# VolCon.net
KiCad netlist of a schematic drawn in EAGLE
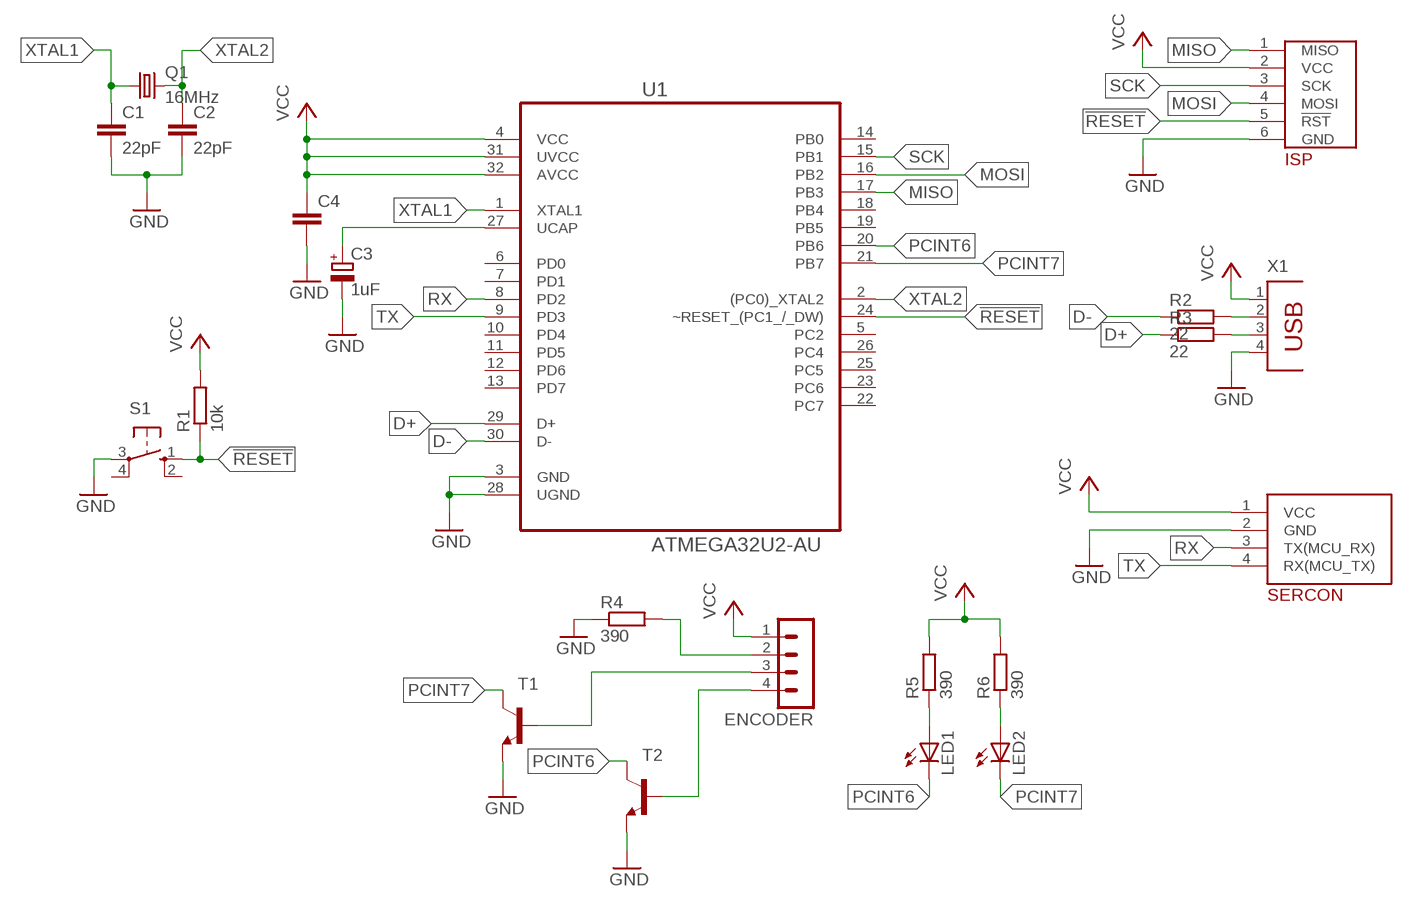
[diagram p0: schematic, sheet 1]

(export (version "E")
  (design (tool "Eeschema 10.0.6"))
  (components
    (comp (ref "C1")
      (value "22pF")
      (footprint "eagle-import:C050-024X044")
      (libsource (lib "eagle-import") (part "C-EU050-024X044"))
    )
    (comp (ref "C2")
      (value "22pF")
      (footprint "eagle-import:C050-024X044")
      (libsource (lib "eagle-import") (part "C-EU050-024X044"))
    )
    (comp (ref "C3")
      (value "1uF")
      (footprint "eagle-import:E5-6")
      (libsource (lib "eagle-import") (part "CPOL-EUE5-6"))
    )
    (comp (ref "C4")
      (value "C-EU050-025X075")
      (footprint "eagle-import:C050-025X075")
      (libsource (lib "eagle-import") (part "C-EU050-025X075"))
    )
    (comp (ref "ENCODER")
      (value "MA04-1")
      (footprint "eagle-import:MA04-1")
      (libsource (lib "eagle-import") (part "MA04-1"))
    )
    (comp (ref "LED1")
      (value "LED5MM")
      (footprint "eagle-import:LED5MM")
      (libsource (lib "eagle-import") (part "LED5MM"))
    )
    (comp (ref "LED2")
      (value "LED5MM")
      (footprint "eagle-import:LED5MM")
      (libsource (lib "eagle-import") (part "LED5MM"))
    )
    (comp (ref "Q1")
      (value "16MHz")
      (footprint "eagle-import:HC49_S")
      (libsource (lib "eagle-import") (part "CRYSTALHC49S"))
    )
    (comp (ref "R1")
      (value "10k")
      (footprint "eagle-import:0204_7")
      (libsource (lib "eagle-import") (part "R-EU_0204/7"))
    )
    (comp (ref "R2")
      (value "22")
      (footprint "eagle-import:0204_7")
      (libsource (lib "eagle-import") (part "R-EU_0204/7"))
    )
    (comp (ref "R3")
      (value "22")
      (footprint "eagle-import:0204_7")
      (libsource (lib "eagle-import") (part "R-EU_0204/7"))
    )
    (comp (ref "R4")
      (value "390")
      (footprint "eagle-import:0204_7")
      (libsource (lib "eagle-import") (part "R-EU_0204/7"))
    )
    (comp (ref "R5")
      (value "390")
      (footprint "eagle-import:0204_7")
      (libsource (lib "eagle-import") (part "R-EU_0204/7"))
    )
    (comp (ref "R6")
      (value "390")
      (footprint "eagle-import:0204_7")
      (libsource (lib "eagle-import") (part "R-EU_0204/7"))
    )
    (comp (ref "S1")
      (value "10-XX")
      (footprint "eagle-import:B3F-10XX")
      (fields (field (name "MPN") "B3F-1000"))
      (libsource (lib "eagle-import") (part "10-XX"))
    )
    (comp (ref "T1")
      (value "2N3565")
      (footprint "eagle-import:TO92")
      (libsource (lib "eagle-import") (part "2N3565"))
    )
    (comp (ref "T2")
      (value "2N3565")
      (footprint "eagle-import:TO92")
      (libsource (lib "eagle-import") (part "2N3565"))
    )
    (comp (ref "U$1")
      (value "ISP-6")
      (footprint "eagle-import:ISP-6")
      (libsource (lib "eagle-import") (part "ISP-6"))
    )
    (comp (ref "U$2")
      (value "SERCON")
      (footprint "eagle-import:SERCON")
      (libsource (lib "eagle-import") (part "SERCON"))
    )
    (comp (ref "U1")
      (value "ATMEGA32U2-AU")
      (footprint "eagle-import:QFP80P900X900X120-32N")
      (libsource (lib "eagle-import") (part "ATMEGA32U2-AU"))
    )
    (comp (ref "X1")
      (value "PN61729")
      (footprint "eagle-import:PN61729")
      (libsource (lib "eagle-import") (part "PN61729"))
    )
  )
  (nets
    (net (code "1") (name "/~{RESET}") (class "Default")
      (node (ref "R1") (pin "1") (pinfunction "1_1") (pintype "passive"))
      (node (ref "S1") (pin "1") (pinfunction "S_1") (pintype "passive"))
      (node (ref "U$1") (pin "5") (pinfunction "~{RST}_5") (pintype "bidirectional"))
      (node (ref "U1") (pin "24") (pinfunction "~{RESET_(PC1_/_DW})_24") (pintype "bidirectional"))
    )
    (net (code "2") (name "D+") (class "Default")
      (node (ref "R3") (pin "1") (pinfunction "1_1") (pintype "passive"))
      (node (ref "U1") (pin "29") (pinfunction "D+_29") (pintype "bidirectional"))
    )
    (net (code "3") (name "D-") (class "Default")
      (node (ref "R2") (pin "1") (pinfunction "1_1") (pintype "passive"))
      (node (ref "U1") (pin "30") (pinfunction "D-_30") (pintype "bidirectional"))
    )
    (net (code "4") (name "GND") (class "Default")
      (node (ref "C1") (pin "2") (pinfunction "2_2") (pintype "passive"))
      (node (ref "C2") (pin "2") (pinfunction "2_2") (pintype "passive"))
      (node (ref "C3") (pin "-") (pinfunction "-_-") (pintype "passive"))
      (node (ref "C4") (pin "2") (pinfunction "2_2") (pintype "passive"))
      (node (ref "R4") (pin "1") (pinfunction "1_1") (pintype "passive"))
      (node (ref "S1") (pin "3") (pinfunction "P_3") (pintype "passive"))
      (node (ref "T1") (pin "3") (pinfunction "E_3") (pintype "passive"))
      (node (ref "T2") (pin "3") (pinfunction "E_3") (pintype "passive"))
      (node (ref "U$1") (pin "6") (pinfunction "GND_6") (pintype "bidirectional"))
      (node (ref "U$2") (pin "2") (pinfunction "GND_2") (pintype "bidirectional"))
      (node (ref "U1") (pin "28") (pinfunction "UGND_28") (pintype "passive"))
      (node (ref "U1") (pin "3") (pinfunction "GND_3") (pintype "passive"))
      (node (ref "X1") (pin "4") (pinfunction "4_4") (pintype "passive"))
    )
    (net (code "5") (name "MISO") (class "Default")
      (node (ref "U$1") (pin "1") (pinfunction "MISO_1") (pintype "bidirectional"))
      (node (ref "U1") (pin "17") (pinfunction "PB3_17") (pintype "bidirectional"))
    )
    (net (code "6") (name "MOSI") (class "Default")
      (node (ref "U$1") (pin "4") (pinfunction "MOSI_4") (pintype "bidirectional"))
      (node (ref "U1") (pin "16") (pinfunction "PB2_16") (pintype "bidirectional"))
    )
    (net (code "7") (name "Net-(ENCODER-Pad2)") (class "Default")
      (node (ref "ENCODER") (pin "2") (pinfunction "2_2") (pintype "passive"))
      (node (ref "R4") (pin "2") (pinfunction "2_2") (pintype "passive"))
    )
    (net (code "8") (name "Net-(LED1-PadA)") (class "Default")
      (node (ref "LED1") (pin "A") (pinfunction "A_A") (pintype "passive"))
      (node (ref "R5") (pin "1") (pinfunction "1_1") (pintype "passive"))
    )
    (net (code "9") (name "Net-(LED2-PadA)") (class "Default")
      (node (ref "LED2") (pin "A") (pinfunction "A_A") (pintype "passive"))
      (node (ref "R6") (pin "1") (pinfunction "1_1") (pintype "passive"))
    )
    (net (code "10") (name "Net-(R2-Pad2)") (class "Default")
      (node (ref "R2") (pin "2") (pinfunction "2_2") (pintype "passive"))
      (node (ref "X1") (pin "2") (pinfunction "2_2") (pintype "passive"))
    )
    (net (code "11") (name "Net-(R3-Pad2)") (class "Default")
      (node (ref "R3") (pin "2") (pinfunction "2_2") (pintype "passive"))
      (node (ref "X1") (pin "3") (pinfunction "3_3") (pintype "passive"))
    )
    (net (code "12") (name "Net-(T1-B)") (class "Default")
      (node (ref "ENCODER") (pin "3") (pinfunction "3_3") (pintype "passive"))
      (node (ref "T1") (pin "2") (pinfunction "B_2") (pintype "passive"))
    )
    (net (code "13") (name "Net-(T2-B)") (class "Default")
      (node (ref "ENCODER") (pin "4") (pinfunction "4_4") (pintype "passive"))
      (node (ref "T2") (pin "2") (pinfunction "B_2") (pintype "passive"))
    )
    (net (code "14") (name "Net-(U1-UCAP)") (class "Default")
      (node (ref "C3") (pin "+") (pinfunction "+_+") (pintype "passive"))
      (node (ref "U1") (pin "27") (pinfunction "UCAP_27") (pintype "power_in"))
    )
    (net (code "15") (name "PCINT6") (class "Default")
      (node (ref "LED1") (pin "K") (pinfunction "C_K") (pintype "passive"))
      (node (ref "T2") (pin "1") (pinfunction "C_1") (pintype "passive"))
      (node (ref "U1") (pin "20") (pinfunction "PB6_20") (pintype "bidirectional"))
    )
    (net (code "16") (name "PCINT7") (class "Default")
      (node (ref "LED2") (pin "K") (pinfunction "C_K") (pintype "passive"))
      (node (ref "T1") (pin "1") (pinfunction "C_1") (pintype "passive"))
      (node (ref "U1") (pin "21") (pinfunction "PB7_21") (pintype "bidirectional"))
    )
    (net (code "17") (name "RX") (class "Default")
      (node (ref "U$2") (pin "3") (pinfunction "TX(MCU_RX)_3") (pintype "bidirectional"))
      (node (ref "U1") (pin "8") (pinfunction "PD2_8") (pintype "bidirectional"))
    )
    (net (code "18") (name "SCK") (class "Default")
      (node (ref "U$1") (pin "3") (pinfunction "SCK_3") (pintype "bidirectional"))
      (node (ref "U1") (pin "15") (pinfunction "PB1_15") (pintype "bidirectional"))
    )
    (net (code "19") (name "TX") (class "Default")
      (node (ref "U$2") (pin "4") (pinfunction "RX(MCU_TX)_4") (pintype "bidirectional"))
      (node (ref "U1") (pin "9") (pinfunction "PD3_9") (pintype "bidirectional"))
    )
    (net (code "20") (name "VCC") (class "Default")
      (node (ref "C4") (pin "1") (pinfunction "1_1") (pintype "passive"))
      (node (ref "ENCODER") (pin "1") (pinfunction "1_1") (pintype "passive"))
      (node (ref "R1") (pin "2") (pinfunction "2_2") (pintype "passive"))
      (node (ref "R5") (pin "2") (pinfunction "2_2") (pintype "passive"))
      (node (ref "R6") (pin "2") (pinfunction "2_2") (pintype "passive"))
      (node (ref "U$1") (pin "2") (pinfunction "VCC_2") (pintype "bidirectional"))
      (node (ref "U$2") (pin "1") (pinfunction "VCC_1") (pintype "bidirectional"))
      (node (ref "U1") (pin "31") (pinfunction "UVCC_31") (pintype "power_in"))
      (node (ref "U1") (pin "32") (pinfunction "AVCC_32") (pintype "power_in"))
      (node (ref "U1") (pin "4") (pinfunction "VCC_4") (pintype "power_in"))
      (node (ref "X1") (pin "1") (pinfunction "1_1") (pintype "passive"))
    )
    (net (code "21") (name "XTAL1") (class "Default")
      (node (ref "C1") (pin "1") (pinfunction "1_1") (pintype "passive"))
      (node (ref "Q1") (pin "1") (pinfunction "1_1") (pintype "passive"))
      (node (ref "U1") (pin "1") (pinfunction "XTAL1_1") (pintype "input"))
    )
    (net (code "22") (name "XTAL2") (class "Default")
      (node (ref "C2") (pin "1") (pinfunction "1_1") (pintype "passive"))
      (node (ref "Q1") (pin "2") (pinfunction "2_2") (pintype "passive"))
      (node (ref "U1") (pin "2") (pinfunction "(PC0)_XTAL2_2") (pintype "bidirectional"))
    )
    (net (code "23") (name "unconnected-(S1-P1-Pad4)") (class "Default")
      (node (ref "S1") (pin "4") (pinfunction "P1_4") (pintype "passive"))
    )
    (net (code "24") (name "unconnected-(S1-S1-Pad2)") (class "Default")
      (node (ref "S1") (pin "2") (pinfunction "S1_2") (pintype "passive"))
    )
    (net (code "25") (name "unconnected-(U1-PB0-Pad14)") (class "Default")
      (node (ref "U1") (pin "14") (pinfunction "PB0_14") (pintype "bidirectional"))
    )
    (net (code "26") (name "unconnected-(U1-PB4-Pad18)") (class "Default")
      (node (ref "U1") (pin "18") (pinfunction "PB4_18") (pintype "bidirectional"))
    )
    (net (code "27") (name "unconnected-(U1-PB5-Pad19)") (class "Default")
      (node (ref "U1") (pin "19") (pinfunction "PB5_19") (pintype "bidirectional"))
    )
    (net (code "28") (name "unconnected-(U1-PC2-Pad5)") (class "Default")
      (node (ref "U1") (pin "5") (pinfunction "PC2_5") (pintype "bidirectional"))
    )
    (net (code "29") (name "unconnected-(U1-PC4-Pad26)") (class "Default")
      (node (ref "U1") (pin "26") (pinfunction "PC4_26") (pintype "bidirectional"))
    )
    (net (code "30") (name "unconnected-(U1-PC5-Pad25)") (class "Default")
      (node (ref "U1") (pin "25") (pinfunction "PC5_25") (pintype "bidirectional"))
    )
    (net (code "31") (name "unconnected-(U1-PC6-Pad23)") (class "Default")
      (node (ref "U1") (pin "23") (pinfunction "PC6_23") (pintype "bidirectional"))
    )
    (net (code "32") (name "unconnected-(U1-PC7-Pad22)") (class "Default")
      (node (ref "U1") (pin "22") (pinfunction "PC7_22") (pintype "bidirectional"))
    )
    (net (code "33") (name "unconnected-(U1-PD0-Pad6)") (class "Default")
      (node (ref "U1") (pin "6") (pinfunction "PD0_6") (pintype "bidirectional"))
    )
    (net (code "34") (name "unconnected-(U1-PD1-Pad7)") (class "Default")
      (node (ref "U1") (pin "7") (pinfunction "PD1_7") (pintype "bidirectional"))
    )
    (net (code "35") (name "unconnected-(U1-PD4-Pad10)") (class "Default")
      (node (ref "U1") (pin "10") (pinfunction "PD4_10") (pintype "bidirectional"))
    )
    (net (code "36") (name "unconnected-(U1-PD5-Pad11)") (class "Default")
      (node (ref "U1") (pin "11") (pinfunction "PD5_11") (pintype "bidirectional"))
    )
    (net (code "37") (name "unconnected-(U1-PD6-Pad12)") (class "Default")
      (node (ref "U1") (pin "12") (pinfunction "PD6_12") (pintype "bidirectional"))
    )
    (net (code "38") (name "unconnected-(U1-PD7-Pad13)") (class "Default")
      (node (ref "U1") (pin "13") (pinfunction "PD7_13") (pintype "bidirectional"))
    )
  )
)
